# Odbiornik_2.net
KiCad netlist of a schematic drawn in EAGLE
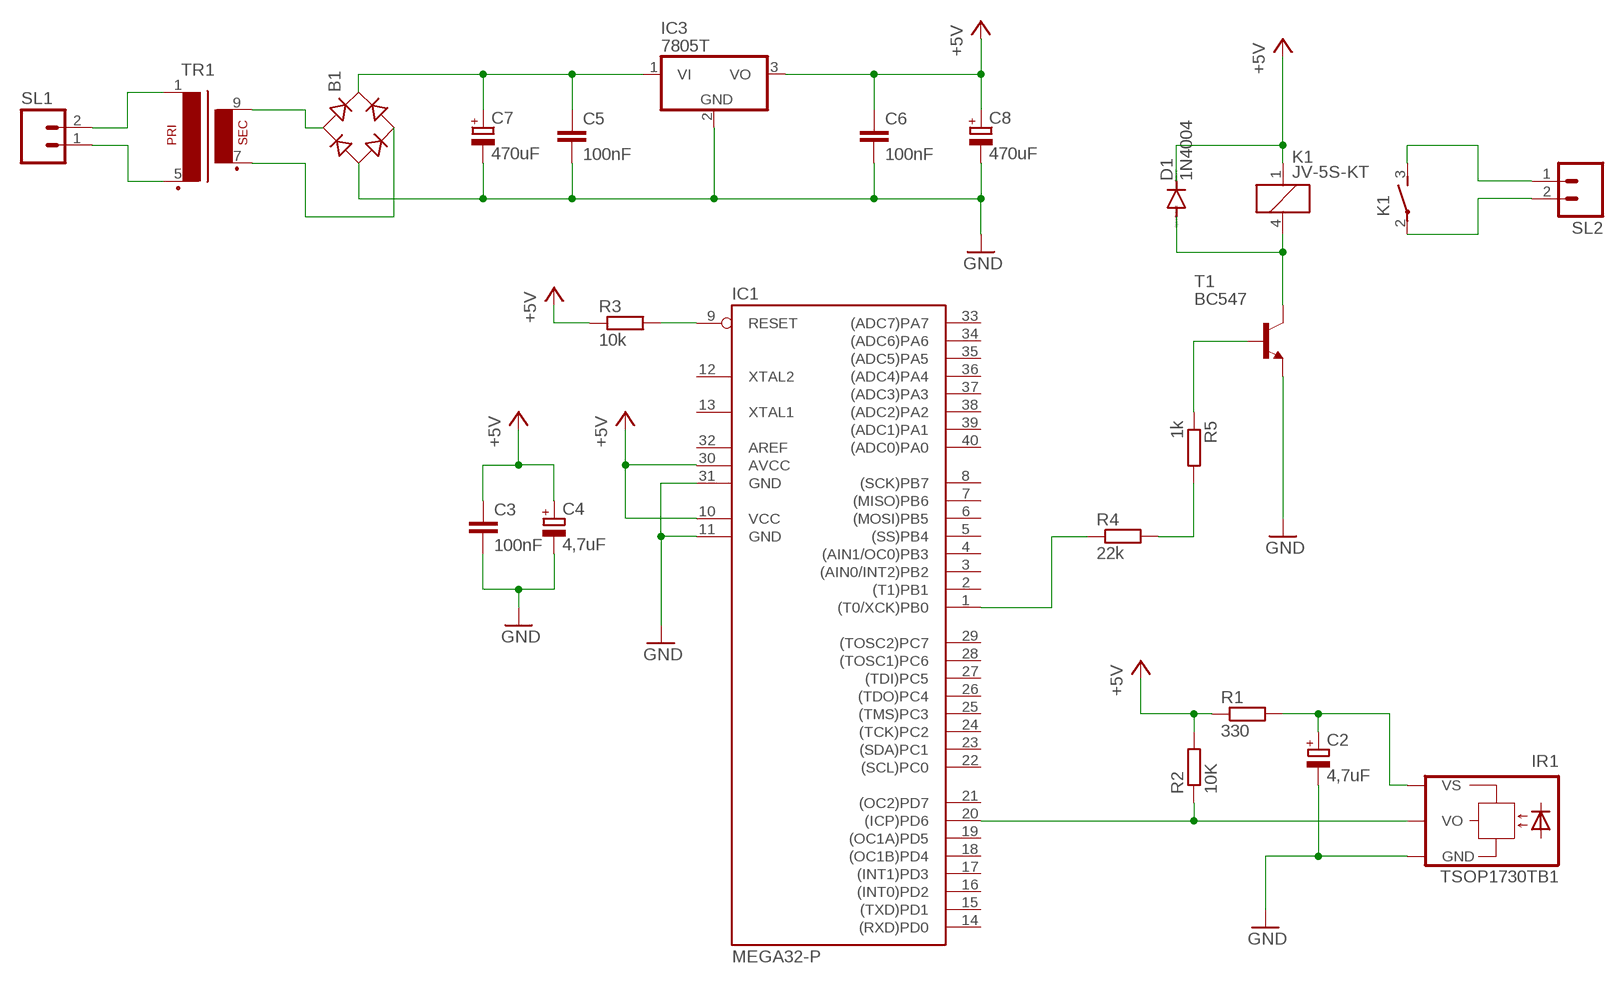
[diagram p0: schematic, sheet 1]

(export (version "E")
  (design (tool "Eeschema 10.0.6"))
  (components
    (comp (ref "B1")
      (value "RB1A")
      (footprint "eagle-import:RB1A")
      (libsource (lib "eagle-import") (part "RB1A"))
    )
    (comp (ref "C2")
      (value "4,7uF")
      (footprint "eagle-import:E2-4")
      (libsource (lib "eagle-import") (part "CPOL-EUE2-4"))
    )
    (comp (ref "C3")
      (value "100nF")
      (footprint "eagle-import:C025-024X044")
      (libsource (lib "eagle-import") (part "C-EU025-024X044"))
    )
    (comp (ref "C4")
      (value "4,7uF")
      (footprint "eagle-import:E2-4")
      (libsource (lib "eagle-import") (part "CPOL-EUE2-4"))
    )
    (comp (ref "C5")
      (value "100nF")
      (footprint "eagle-import:C025-024X044")
      (libsource (lib "eagle-import") (part "C-EU025-024X044"))
    )
    (comp (ref "C6")
      (value "100nF")
      (footprint "eagle-import:C025-024X044")
      (libsource (lib "eagle-import") (part "C-EU025-024X044"))
    )
    (comp (ref "C7")
      (value "470uF")
      (footprint "eagle-import:E2-4")
      (libsource (lib "eagle-import") (part "CPOL-EUE2-4"))
    )
    (comp (ref "C8")
      (value "470uF")
      (footprint "eagle-import:E2-4")
      (libsource (lib "eagle-import") (part "CPOL-EUE2-4"))
    )
    (comp (ref "D1")
      (value "1N4004")
      (footprint "eagle-import:DO41-10")
      (libsource (lib "eagle-import") (part "1N4004"))
    )
    (comp (ref "IC1")
      (value "MEGA32-P")
      (footprint "eagle-import:DIL40")
      (fields (field (name "MPN") "ATMEGA32-16PU"))
      (libsource (lib "eagle-import") (part "MEGA32-P"))
    )
    (comp (ref "IC3")
      (value "7805T")
      (footprint "eagle-import:TO220H")
      (libsource (lib "eagle-import") (part "78T05"))
    )
    (comp (ref "IR1")
      (value "TSOP1730TB1")
      (footprint "eagle-import:TSOP17_TB1")
      (libsource (lib "eagle-import") (part "TSOP17TB130"))
    )
    (comp (ref "K1")
      (value "JV-5S-KT")
      (footprint "eagle-import:JV-KT")
      (libsource (lib "eagle-import") (part "JV-KT-5S"))
    )
    (comp (ref "R1")
      (value "330")
      (footprint "eagle-import:0204_5")
      (libsource (lib "eagle-import") (part "R-EU_0204/5"))
    )
    (comp (ref "R2")
      (value "10K")
      (footprint "eagle-import:0204_5")
      (libsource (lib "eagle-import") (part "R-EU_0204/5"))
    )
    (comp (ref "R3")
      (value "10k")
      (footprint "eagle-import:0204_5")
      (libsource (lib "eagle-import") (part "R-EU_0204/5"))
    )
    (comp (ref "R4")
      (value "22k")
      (footprint "eagle-import:0204_5")
      (libsource (lib "eagle-import") (part "R-EU_0204/5"))
    )
    (comp (ref "R5")
      (value "1k")
      (footprint "eagle-import:0204_5")
      (libsource (lib "eagle-import") (part "R-EU_0204/5"))
    )
    (comp (ref "SL1")
      (value "M02")
      (footprint "eagle-import:02P")
      (libsource (lib "eagle-import") (part "M02"))
    )
    (comp (ref "SL2")
      (value "M02")
      (footprint "eagle-import:02P")
      (libsource (lib "eagle-import") (part "M02"))
    )
    (comp (ref "T1")
      (value "BC547")
      (footprint "eagle-import:TO92")
      (libsource (lib "eagle-import") (part "BC547"))
    )
    (comp (ref "TR1")
      (value "EI42-1")
      (footprint "eagle-import:EI42-1")
      (libsource (lib "eagle-import") (part "EI42-1"))
    )
  )
  (nets
    (net (code "1") (name "+5V") (class "Default")
      (node (ref "C3") (pin "1") (pinfunction "1_1") (pintype "passive"))
      (node (ref "C4") (pin "+") (pinfunction "+_+") (pintype "passive"))
      (node (ref "C6") (pin "1") (pinfunction "1_1") (pintype "passive"))
      (node (ref "C8") (pin "+") (pinfunction "+_+") (pintype "passive"))
      (node (ref "D1") (pin "C") (pinfunction "C_C") (pintype "passive"))
      (node (ref "IC1") (pin "10") (pinfunction "VCC_10") (pintype "power_in"))
      (node (ref "IC1") (pin "30") (pinfunction "AVCC_30") (pintype "power_in"))
      (node (ref "IC3") (pin "3") (pinfunction "VO_3") (pintype "passive"))
      (node (ref "K1") (pin "1") (pinfunction "1_1") (pintype "passive"))
      (node (ref "R1") (pin "1") (pinfunction "1_1") (pintype "passive"))
      (node (ref "R2") (pin "2") (pinfunction "2_2") (pintype "passive"))
      (node (ref "R3") (pin "1") (pinfunction "1_1") (pintype "passive"))
    )
    (net (code "2") (name "GND") (class "Default")
      (node (ref "B1") (pin "-") (pinfunction "-_-") (pintype "passive"))
      (node (ref "C2") (pin "-") (pinfunction "-_-") (pintype "passive"))
      (node (ref "C3") (pin "2") (pinfunction "2_2") (pintype "passive"))
      (node (ref "C4") (pin "-") (pinfunction "-_-") (pintype "passive"))
      (node (ref "C5") (pin "2") (pinfunction "2_2") (pintype "passive"))
      (node (ref "C6") (pin "2") (pinfunction "2_2") (pintype "passive"))
      (node (ref "C7") (pin "-") (pinfunction "-_-") (pintype "passive"))
      (node (ref "C8") (pin "-") (pinfunction "-_-") (pintype "passive"))
      (node (ref "IC1") (pin "11") (pinfunction "GND_11") (pintype "power_in"))
      (node (ref "IC1") (pin "31") (pinfunction "GND_31") (pintype "power_in"))
      (node (ref "IC3") (pin "2") (pinfunction "GND_2") (pintype "passive"))
      (node (ref "IR1") (pin "GND") (pinfunction "GND_GND") (pintype "power_in"))
      (node (ref "T1") (pin "1") (pinfunction "E_1") (pintype "passive"))
    )
    (net (code "3") (name "Net-(C2-Pad+)") (class "Default")
      (node (ref "C2") (pin "+") (pinfunction "+_+") (pintype "passive"))
      (node (ref "IR1") (pin "VS") (pinfunction "VS_VS") (pintype "power_in"))
      (node (ref "R1") (pin "2") (pinfunction "2_2") (pintype "passive"))
    )
    (net (code "4") (name "Net-(IC1-(ICP)PD6)") (class "Default")
      (node (ref "IC1") (pin "20") (pinfunction "(ICP)PD6_20") (pintype "bidirectional"))
      (node (ref "IR1") (pin "VO") (pinfunction "VO_VO") (pintype "open_collector"))
      (node (ref "R2") (pin "1") (pinfunction "1_1") (pintype "passive"))
    )
    (net (code "5") (name "Net-(IC1-(T0{slash}XCK)PB0)") (class "Default")
      (node (ref "IC1") (pin "1") (pinfunction "(T0/XCK)PB0_1") (pintype "bidirectional"))
      (node (ref "R4") (pin "1") (pinfunction "1_1") (pintype "passive"))
    )
    (net (code "6") (name "Net-(IC1-RESET)") (class "Default")
      (node (ref "IC1") (pin "9") (pinfunction "RESET_9") (pintype "input"))
      (node (ref "R3") (pin "2") (pinfunction "2_2") (pintype "passive"))
    )
    (net (code "7") (name "Net-(IC3-VI)") (class "Default")
      (node (ref "B1") (pin "+") (pinfunction "+_+") (pintype "passive"))
      (node (ref "C5") (pin "1") (pinfunction "1_1") (pintype "passive"))
      (node (ref "C7") (pin "+") (pinfunction "+_+") (pintype "passive"))
      (node (ref "IC3") (pin "1") (pinfunction "VI_1") (pintype "input"))
    )
    (net (code "8") (name "Net-(K1A-2)") (class "Default")
      (node (ref "D1") (pin "A") (pinfunction "A_A") (pintype "passive"))
      (node (ref "K1") (pin "4") (pinfunction "2_4") (pintype "passive"))
      (node (ref "T1") (pin "3") (pinfunction "C_3") (pintype "passive"))
    )
    (net (code "9") (name "Net-(K1B-P)") (class "Default")
      (node (ref "K1") (pin "2") (pinfunction "P_2") (pintype "passive"))
      (node (ref "SL2") (pin "2") (pinfunction "2_2") (pintype "passive"))
    )
    (net (code "10") (name "Net-(K1B-S)") (class "Default")
      (node (ref "K1") (pin "3") (pinfunction "S_3") (pintype "passive"))
      (node (ref "SL2") (pin "1") (pinfunction "1_1") (pintype "passive"))
    )
    (net (code "11") (name "Net-(R4-Pad2)") (class "Default")
      (node (ref "R4") (pin "2") (pinfunction "2_2") (pintype "passive"))
      (node (ref "R5") (pin "2") (pinfunction "2_2") (pintype "passive"))
    )
    (net (code "12") (name "Net-(T1-B)") (class "Default")
      (node (ref "R5") (pin "1") (pinfunction "1_1") (pintype "passive"))
      (node (ref "T1") (pin "2") (pinfunction "B_2") (pintype "passive"))
    )
    (net (code "13") (name "Net-(TR1-P1)") (class "Default")
      (node (ref "SL1") (pin "2") (pinfunction "2_2") (pintype "passive"))
      (node (ref "TR1") (pin "1") (pinfunction "P1_1") (pintype "passive"))
    )
    (net (code "14") (name "Net-(TR1-P2)") (class "Default")
      (node (ref "SL1") (pin "1") (pinfunction "1_1") (pintype "passive"))
      (node (ref "TR1") (pin "5") (pinfunction "P2_5") (pintype "passive"))
    )
    (net (code "15") (name "Net-(TR1-S3)") (class "Default")
      (node (ref "B1") (pin "AC2") (pinfunction "AC2_AC2") (pintype "passive"))
      (node (ref "TR1") (pin "7") (pinfunction "S3_7") (pintype "passive"))
    )
    (net (code "16") (name "Net-(TR1-S4)") (class "Default")
      (node (ref "B1") (pin "AC1") (pinfunction "AC1_AC1") (pintype "passive"))
      (node (ref "TR1") (pin "9") (pinfunction "S4_9") (pintype "passive"))
    )
    (net (code "17") (name "unconnected-(IC1-(ADC0)PA0-Pad40)") (class "Default")
      (node (ref "IC1") (pin "40") (pinfunction "(ADC0)PA0_40") (pintype "bidirectional"))
    )
    (net (code "18") (name "unconnected-(IC1-(ADC1)PA1-Pad39)") (class "Default")
      (node (ref "IC1") (pin "39") (pinfunction "(ADC1)PA1_39") (pintype "bidirectional"))
    )
    (net (code "19") (name "unconnected-(IC1-(ADC2)PA2-Pad38)") (class "Default")
      (node (ref "IC1") (pin "38") (pinfunction "(ADC2)PA2_38") (pintype "bidirectional"))
    )
    (net (code "20") (name "unconnected-(IC1-(ADC3)PA3-Pad37)") (class "Default")
      (node (ref "IC1") (pin "37") (pinfunction "(ADC3)PA3_37") (pintype "bidirectional"))
    )
    (net (code "21") (name "unconnected-(IC1-(ADC4)PA4-Pad36)") (class "Default")
      (node (ref "IC1") (pin "36") (pinfunction "(ADC4)PA4_36") (pintype "bidirectional"))
    )
    (net (code "22") (name "unconnected-(IC1-(ADC5)PA5-Pad35)") (class "Default")
      (node (ref "IC1") (pin "35") (pinfunction "(ADC5)PA5_35") (pintype "bidirectional"))
    )
    (net (code "23") (name "unconnected-(IC1-(ADC6)PA6-Pad34)") (class "Default")
      (node (ref "IC1") (pin "34") (pinfunction "(ADC6)PA6_34") (pintype "bidirectional"))
    )
    (net (code "24") (name "unconnected-(IC1-(ADC7)PA7-Pad33)") (class "Default")
      (node (ref "IC1") (pin "33") (pinfunction "(ADC7)PA7_33") (pintype "bidirectional"))
    )
    (net (code "25") (name "unconnected-(IC1-(AIN0{slash}INT2)PB2-Pad3)") (class "Default")
      (node (ref "IC1") (pin "3") (pinfunction "(AIN0/INT2)PB2_3") (pintype "bidirectional"))
    )
    (net (code "26") (name "unconnected-(IC1-(AIN1{slash}OC0)PB3-Pad4)") (class "Default")
      (node (ref "IC1") (pin "4") (pinfunction "(AIN1/OC0)PB3_4") (pintype "bidirectional"))
    )
    (net (code "27") (name "unconnected-(IC1-(INT0)PD2-Pad16)") (class "Default")
      (node (ref "IC1") (pin "16") (pinfunction "(INT0)PD2_16") (pintype "bidirectional"))
    )
    (net (code "28") (name "unconnected-(IC1-(INT1)PD3-Pad17)") (class "Default")
      (node (ref "IC1") (pin "17") (pinfunction "(INT1)PD3_17") (pintype "bidirectional"))
    )
    (net (code "29") (name "unconnected-(IC1-(MISO)PB6-Pad7)") (class "Default")
      (node (ref "IC1") (pin "7") (pinfunction "(MISO)PB6_7") (pintype "bidirectional"))
    )
    (net (code "30") (name "unconnected-(IC1-(MOSI)PB5-Pad6)") (class "Default")
      (node (ref "IC1") (pin "6") (pinfunction "(MOSI)PB5_6") (pintype "bidirectional"))
    )
    (net (code "31") (name "unconnected-(IC1-(OC1A)PD5-Pad19)") (class "Default")
      (node (ref "IC1") (pin "19") (pinfunction "(OC1A)PD5_19") (pintype "bidirectional"))
    )
    (net (code "32") (name "unconnected-(IC1-(OC1B)PD4-Pad18)") (class "Default")
      (node (ref "IC1") (pin "18") (pinfunction "(OC1B)PD4_18") (pintype "bidirectional"))
    )
    (net (code "33") (name "unconnected-(IC1-(OC2)PD7-Pad21)") (class "Default")
      (node (ref "IC1") (pin "21") (pinfunction "(OC2)PD7_21") (pintype "bidirectional"))
    )
    (net (code "34") (name "unconnected-(IC1-(RXD)PD0-Pad14)") (class "Default")
      (node (ref "IC1") (pin "14") (pinfunction "(RXD)PD0_14") (pintype "bidirectional"))
    )
    (net (code "35") (name "unconnected-(IC1-(SCK)PB7-Pad8)") (class "Default")
      (node (ref "IC1") (pin "8") (pinfunction "(SCK)PB7_8") (pintype "bidirectional"))
    )
    (net (code "36") (name "unconnected-(IC1-(SCL)PC0-Pad22)") (class "Default")
      (node (ref "IC1") (pin "22") (pinfunction "(SCL)PC0_22") (pintype "bidirectional"))
    )
    (net (code "37") (name "unconnected-(IC1-(SDA)PC1-Pad23)") (class "Default")
      (node (ref "IC1") (pin "23") (pinfunction "(SDA)PC1_23") (pintype "bidirectional"))
    )
    (net (code "38") (name "unconnected-(IC1-(SS)PB4-Pad5)") (class "Default")
      (node (ref "IC1") (pin "5") (pinfunction "(SS)PB4_5") (pintype "bidirectional"))
    )
    (net (code "39") (name "unconnected-(IC1-(T1)PB1-Pad2)") (class "Default")
      (node (ref "IC1") (pin "2") (pinfunction "(T1)PB1_2") (pintype "bidirectional"))
    )
    (net (code "40") (name "unconnected-(IC1-(TCK)PC2-Pad24)") (class "Default")
      (node (ref "IC1") (pin "24") (pinfunction "(TCK)PC2_24") (pintype "bidirectional"))
    )
    (net (code "41") (name "unconnected-(IC1-(TDI)PC5-Pad27)") (class "Default")
      (node (ref "IC1") (pin "27") (pinfunction "(TDI)PC5_27") (pintype "bidirectional"))
    )
    (net (code "42") (name "unconnected-(IC1-(TDO)PC4-Pad26)") (class "Default")
      (node (ref "IC1") (pin "26") (pinfunction "(TDO)PC4_26") (pintype "bidirectional"))
    )
    (net (code "43") (name "unconnected-(IC1-(TMS)PC3-Pad25)") (class "Default")
      (node (ref "IC1") (pin "25") (pinfunction "(TMS)PC3_25") (pintype "bidirectional"))
    )
    (net (code "44") (name "unconnected-(IC1-(TOSC1)PC6-Pad28)") (class "Default")
      (node (ref "IC1") (pin "28") (pinfunction "(TOSC1)PC6_28") (pintype "bidirectional"))
    )
    (net (code "45") (name "unconnected-(IC1-(TOSC2)PC7-Pad29)") (class "Default")
      (node (ref "IC1") (pin "29") (pinfunction "(TOSC2)PC7_29") (pintype "bidirectional"))
    )
    (net (code "46") (name "unconnected-(IC1-(TXD)PD1-Pad15)") (class "Default")
      (node (ref "IC1") (pin "15") (pinfunction "(TXD)PD1_15") (pintype "bidirectional"))
    )
    (net (code "47") (name "unconnected-(IC1-AREF-Pad32)") (class "Default")
      (node (ref "IC1") (pin "32") (pinfunction "AREF_32") (pintype "passive"))
    )
    (net (code "48") (name "unconnected-(IC1-XTAL1-Pad13)") (class "Default")
      (node (ref "IC1") (pin "13") (pinfunction "XTAL1_13") (pintype "bidirectional"))
    )
    (net (code "49") (name "unconnected-(IC1-XTAL2-Pad12)") (class "Default")
      (node (ref "IC1") (pin "12") (pinfunction "XTAL2_12") (pintype "bidirectional"))
    )
  )
)
